# Sheet1_-.net
KiCad netlist of a schematic drawn in Altium Designer
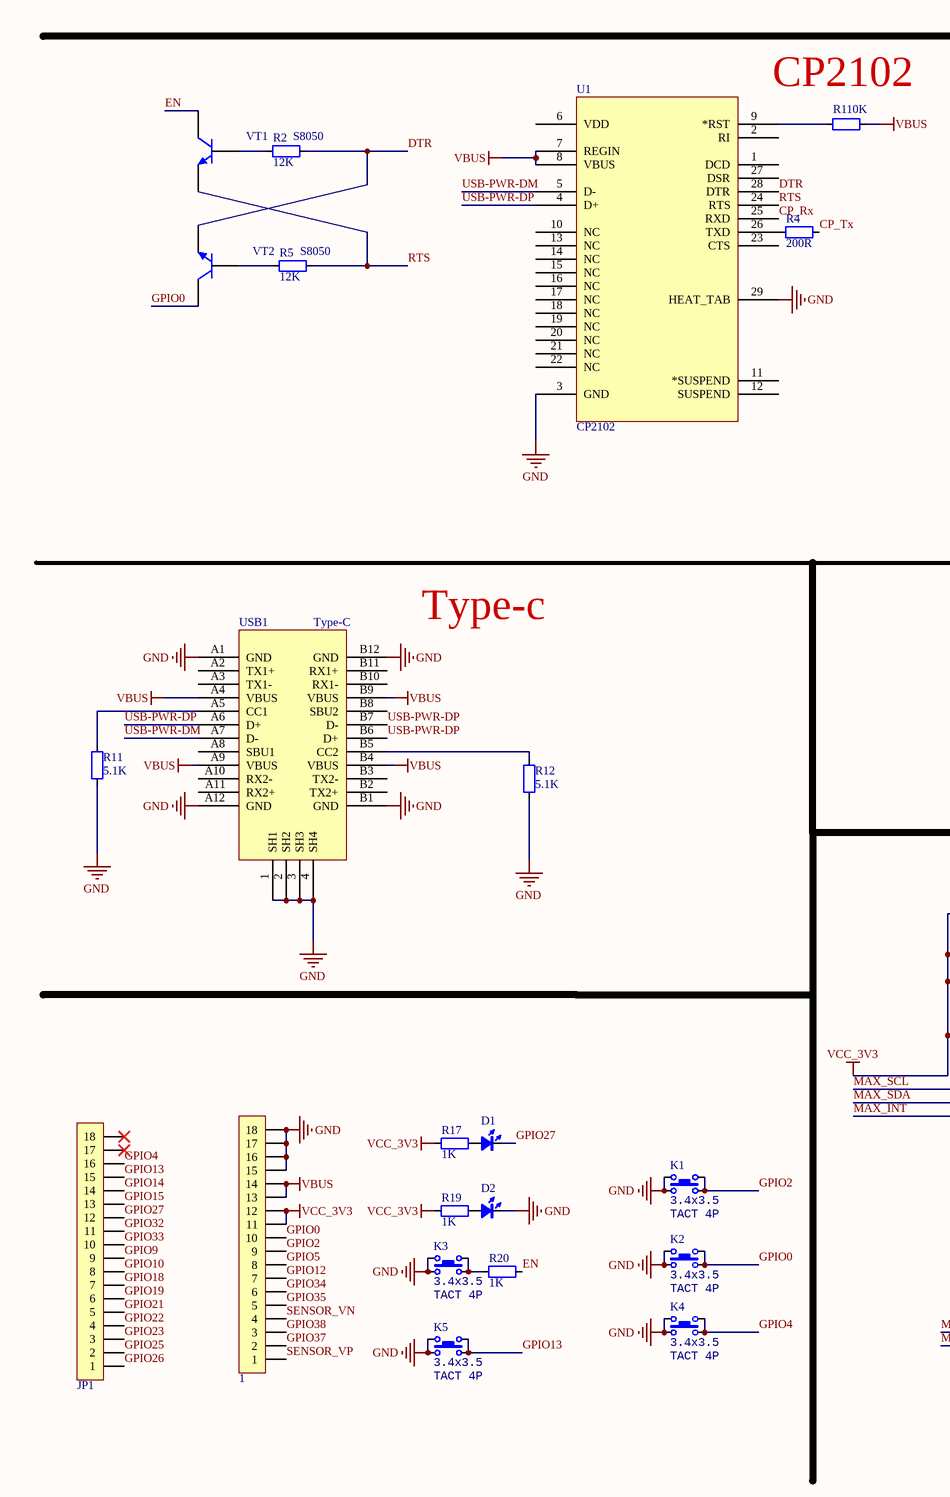
[diagram p0: Sheet1 - 副本.SchDoc, left]
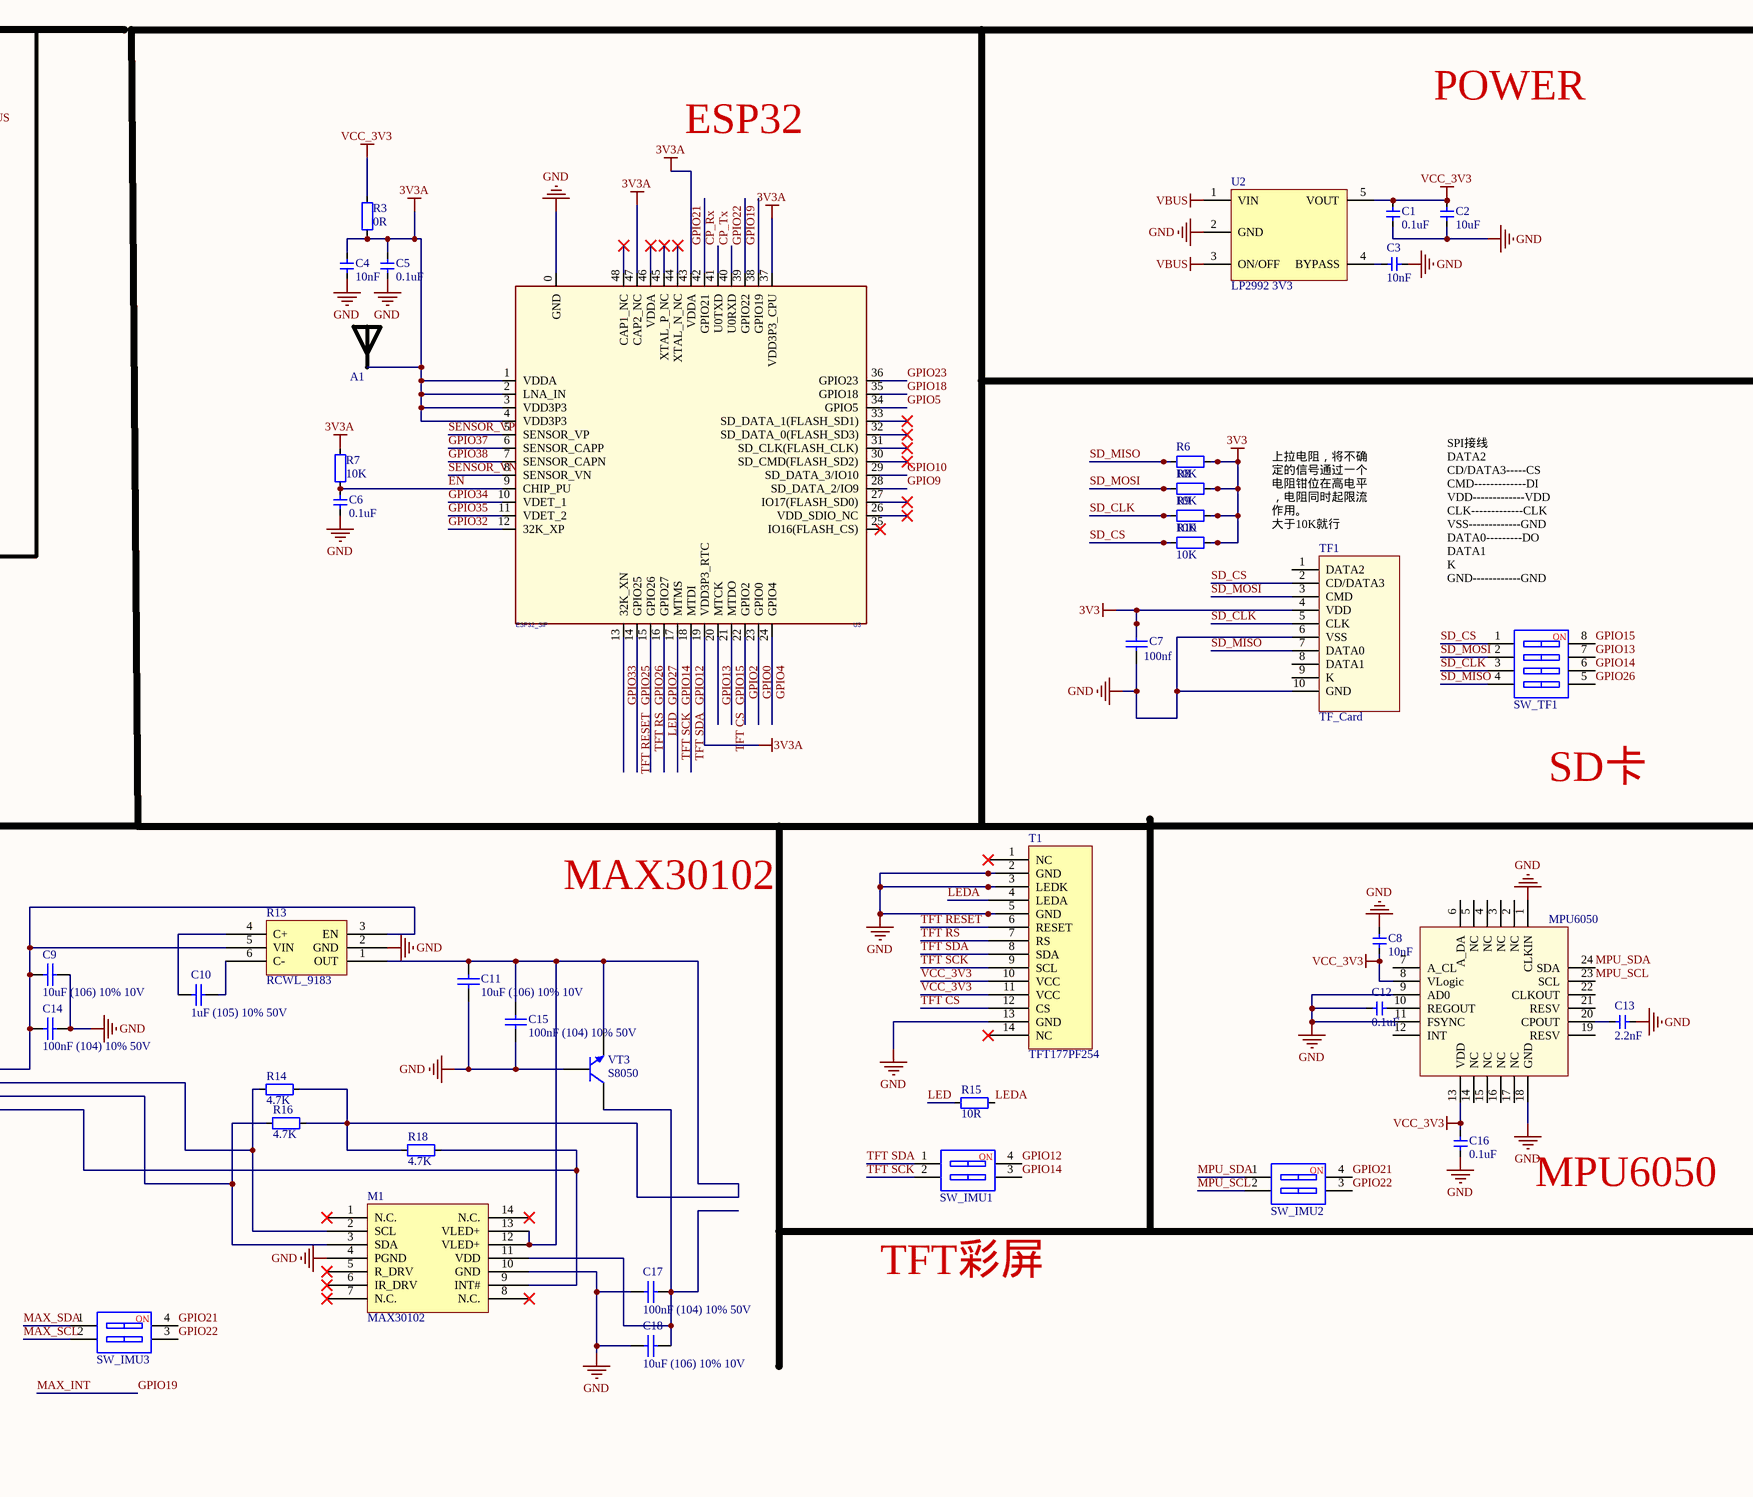
[diagram p1: Sheet1 - 副本.SchDoc, right]

(export (version "E")
  (design (tool "Eeschema 10.0.6"))
  (components
    (comp (ref "1")
      (value "HDR-1X18")
      (footprint "HDR2.54-LI-18P")
      (description "18P接插件")
      (libsource (lib "5.4 - 接插件-脚距2.54 (100mil) ") (part "Header 18"))
    )
    (comp (ref "A1")
      (value "RAINSUN")
      (footprint "ANT-Rainsun-AN5120")
      (libsource (lib "ESP32-PicoDK") (part "ANT-Rainsun-AP5120"))
    )
    (comp (ref "C1")
      (value "0.1uF")
      (footprint "0603_C")
      (description "Capacitor")
      (libsource (lib "MyPcbLib") (part "电容-0402"))
    )
    (comp (ref "C2")
      (value "10uF")
      (footprint "0603_C")
      (description "Capacitor")
      (libsource (lib "MyPcbLib") (part "电容-0402"))
    )
    (comp (ref "C3")
      (value "10nF")
      (footprint "0603_C")
      (description "Capacitor")
      (libsource (lib "MyPcbLib") (part "电容-0402"))
    )
    (comp (ref "C4")
      (value "10nF")
      (footprint "0603_C")
      (description "Capacitor")
      (libsource (lib "ESP32-PicoDK") (part "电容-0402_2"))
    )
    (comp (ref "C5")
      (value "0.1uF")
      (footprint "0603_C")
      (description "Capacitor")
      (libsource (lib "ESP32-PicoDK") (part "电容-0402_1"))
    )
    (comp (ref "C6")
      (value "0.1uF")
      (footprint "0603_C")
      (description "Capacitor")
      (libsource (lib "ESP32-PicoDK") (part "电容-0402_1"))
    )
    (comp (ref "C7")
      (value "100nf")
      (footprint "0603_C")
      (description "Capacitor")
      (libsource (lib "0.1 - 电阻-电容-电感-电位器") (part "C"))
    )
    (comp (ref "C8")
      (value "10nF")
      (footprint "0603_C")
      (description "Capacitor")
      (libsource (lib "MyPcbLib") (part "电容-0402"))
    )
    (comp (ref "C9")
      (value "10uF (106) 10% 10V")
      (footprint "0603_C")
      (description "贴片电容")
      (libsource (lib "Miscellaneous Devices LC") (part "0603 10uF (106) 10% 10V"))
    )
    (comp (ref "C10")
      (value "1uF (105) 10% 50V")
      (footprint "0603_C")
      (description "贴片电容")
      (libsource (lib "Miscellaneous Devices LC") (part "0603 1uF (105) 10% 50V"))
    )
    (comp (ref "C11")
      (value "10uF (106) 10% 10V")
      (footprint "0603_C")
      (description "贴片电容")
      (libsource (lib "Miscellaneous Devices LC") (part "0603 10uF (106) 10% 10V"))
    )
    (comp (ref "C12")
      (value "0.1uF")
      (footprint "0603_C")
      (description "Capacitor")
      (libsource (lib "MyPcbLib") (part "电容-0402"))
    )
    (comp (ref "C13")
      (value "2.2nF")
      (footprint "0603_C")
      (description "Capacitor")
      (libsource (lib "MyPcbLib") (part "电容-0402"))
    )
    (comp (ref "C14")
      (value "100nF (104) 10% 50V")
      (footprint "0603_C")
      (description "贴片电容")
      (libsource (lib "Miscellaneous Devices LC") (part "0603 100nF (104) 10% 50V"))
    )
    (comp (ref "C15")
      (value "100nF (104) 10% 50V")
      (footprint "0603_C")
      (description "贴片电容")
      (libsource (lib "Miscellaneous Devices LC") (part "0603 100nF (104) 10% 50V"))
    )
    (comp (ref "C16")
      (value "0.1uF")
      (footprint "0603_C")
      (description "Capacitor")
      (libsource (lib "MyPcbLib") (part "电容-0402"))
    )
    (comp (ref "C17")
      (value "100nF (104) 10% 50V")
      (footprint "0603_C")
      (description "贴片电容")
      (libsource (lib "Miscellaneous Devices LC") (part "0603 100nF (104) 10% 50V"))
    )
    (comp (ref "C18")
      (value "10uF (106) 10% 10V")
      (footprint "0603_C")
      (description "贴片电容")
      (libsource (lib "Miscellaneous Devices LC") (part "0603 10uF (106) 10% 10V"))
    )
    (comp (ref "D1")
      (value "color?")
      (footprint "LED_0402_RED")
      (description "LED")
      (libsource (lib "KitSprout") (part "LED_0402"))
    )
    (comp (ref "D2")
      (value "color?")
      (footprint "LED_0402_RED")
      (description "LED")
      (libsource (lib "KitSprout") (part "LED_0402"))
    )
    (comp (ref "JP1")
      (value "HDR-1X18")
      (footprint "HDR2.54-LI-18P")
      (description "18P接插件")
      (libsource (lib "5.4 - 接插件-脚距2.54 (100mil) ") (part "Header 18"))
    )
    (comp (ref "K1")
      (value "3.4x3.5")
      (footprint "ButtonTACT_3.5*3.55_90")
      (description "Button")
      (fields (field (name "TYPE") "TACT 4P") (field (name "Comment") "TACT 4P"))
      (libsource (lib "KitSprout") (part "ButtonTACT"))
    )
    (comp (ref "K2")
      (value "3.4x3.5")
      (footprint "ButtonTACT_3.5*3.55_90")
      (description "Button")
      (fields (field (name "TYPE") "TACT 4P") (field (name "Comment") "TACT 4P"))
      (libsource (lib "KitSprout") (part "ButtonTACT"))
    )
    (comp (ref "K3")
      (value "3.4x3.5")
      (footprint "ButtonTACT_3.5*3.55_90")
      (description "Button")
      (fields (field (name "TYPE") "TACT 4P") (field (name "Comment") "TACT 4P"))
      (libsource (lib "KitSprout") (part "ButtonTACT"))
    )
    (comp (ref "K4")
      (value "3.4x3.5")
      (footprint "ButtonTACT_3.5*3.55_90")
      (description "Button")
      (fields (field (name "TYPE") "TACT 4P") (field (name "Comment") "TACT 4P"))
      (libsource (lib "KitSprout") (part "ButtonTACT"))
    )
    (comp (ref "K5")
      (value "3.4x3.5")
      (footprint "ButtonTACT_3.5*3.55_90")
      (description "Button")
      (fields (field (name "TYPE") "TACT 4P") (field (name "Comment") "TACT 4P"))
      (libsource (lib "KitSprout") (part "ButtonTACT"))
    )
    (comp (ref "M1")
      (value "MAX30102")
      (footprint "MAX30102")
      (libsource (lib "ESP32-PicoDK") (part "MAX30102"))
    )
    (comp (ref "R1")
      (value "10K")
      (footprint "0603_R")
      (description "Resistor")
      (libsource (lib "") (part "电阻-0402_1_1"))
    )
    (comp (ref "R2")
      (value "12K")
      (footprint "0603_R")
      (description "Resistor")
      (libsource (lib "ESP32-PicoDK") (part "电阻-0402"))
    )
    (comp (ref "R3")
      (value "0R")
      (footprint "0603_R")
      (description "Resistor")
      (libsource (lib "ESP32-PicoDK") (part "电阻-0402_3"))
    )
    (comp (ref "R4")
      (value "200R")
      (footprint "0603_R")
      (description "Resistor")
      (libsource (lib "ESP32-PicoDK") (part "电阻-0402_2"))
    )
    (comp (ref "R5")
      (value "12K")
      (footprint "0603_R")
      (description "Resistor")
      (libsource (lib "ESP32-PicoDK") (part "电阻-0402"))
    )
    (comp (ref "R6")
      (value "10K")
      (footprint "0603_R")
      (description "贴片电阻")
      (libsource (lib "0.1 - 电阻-电容-电感-电位器") (part "R"))
    )
    (comp (ref "R7")
      (value "10K")
      (footprint "0603_R")
      (description "Resistor")
      (libsource (lib "ESP32-PicoDK") (part "电阻-0402_1"))
    )
    (comp (ref "R8")
      (value "10K")
      (footprint "0603_R")
      (description "贴片电阻")
      (libsource (lib "0.1 - 电阻-电容-电感-电位器") (part "R"))
    )
    (comp (ref "R9")
      (value "10K")
      (footprint "0603_R")
      (description "贴片电阻")
      (libsource (lib "0.1 - 电阻-电容-电感-电位器") (part "R"))
    )
    (comp (ref "R10")
      (value "10K")
      (footprint "0603_R")
      (description "贴片电阻")
      (libsource (lib "0.1 - 电阻-电容-电感-电位器") (part "R"))
    )
    (comp (ref "R11")
      (value "5.1K")
      (footprint "0603_R")
      (description "Resistor")
      (libsource (lib "ESP32-PicoDK") (part "电阻-0402_7"))
    )
    (comp (ref "R12")
      (value "5.1K")
      (footprint "0603_R")
      (description "Resistor")
      (libsource (lib "ESP32-PicoDK") (part "电阻-0402_7"))
    )
    (comp (ref "R13")
      (value "RCWL_9183")
      (footprint "RCWL-9183")
      (libsource (lib "ESP32-PicoDK") (part "RCWL_9183"))
    )
    (comp (ref "R14")
      (value "4.7K")
      (footprint "0603_R")
      (description "Resistor")
      (libsource (lib "ESP32-PicoDK") (part "电阻-0402_6"))
    )
    (comp (ref "R15")
      (value "10R")
      (footprint "0603_R")
      (description "Resistor")
      (libsource (lib "ESP32-PicoDK") (part "电阻-0402_9"))
    )
    (comp (ref "R16")
      (value "4.7K")
      (footprint "0603_R")
      (description "Resistor")
      (libsource (lib "ESP32-PicoDK") (part "电阻-0402_6"))
    )
    (comp (ref "R17")
      (value "1K")
      (footprint "0603_R")
      (description "Resistor")
      (libsource (lib "MyPcbLib") (part "电阻-0402"))
    )
    (comp (ref "R18")
      (value "4.7K")
      (footprint "0603_R")
      (description "Resistor")
      (libsource (lib "ESP32-PicoDK") (part "电阻-0402_6"))
    )
    (comp (ref "R19")
      (value "1K")
      (footprint "0603_R")
      (description "Resistor")
      (libsource (lib "MyPcbLib") (part "电阻-0402"))
    )
    (comp (ref "R20")
      (value "1K")
      (footprint "0603_R")
      (description "Resistor")
      (libsource (lib "MyPcbLib") (part "电阻-0402"))
    )
    (comp (ref "SW_IMU1")
      (value "SW-2P")
      (footprint "SW1.27 SMD-2P")
      (description "2路编码开关")
      (libsource (lib "0.7 - 常用按键-开关-蜂鸣器-电池-测试点") (part "SW-2P"))
    )
    (comp (ref "SW_IMU2")
      (value "SW-2P")
      (footprint "SW1.27 SMD-2P")
      (description "2路编码开关")
      (libsource (lib "0.7 - 常用按键-开关-蜂鸣器-电池-测试点") (part "SW-2P"))
    )
    (comp (ref "SW_IMU3")
      (value "SW-2P")
      (footprint "SW1.27 SMD-2P")
      (description "2路编码开关")
      (libsource (lib "0.7 - 常用按键-开关-蜂鸣器-电池-测试点") (part "SW-2P"))
    )
    (comp (ref "SW_TF1")
      (value "SW-4P")
      (footprint "SW1.27 SMD-4P")
      (description "4路编码开关")
      (libsource (lib "0.7 - 常用按键-开关-蜂鸣器-电池-测试点") (part "SW-4P"))
    )
    (comp (ref "T1")
      (value "TFT177PF254")
      (footprint "TFT144PF254")
      (libsource (lib "ESP32-PicoDK") (part "TFT177PF254"))
    )
    (comp (ref "TF1")
      (value "TF_Card")
      (footprint "Micro SD")
      (description "TF卡座")
      (libsource (lib "0.8 - 以太网-音频-Type-C USB插座") (part "TF_Card"))
    )
    (comp (ref "U1")
      (value "CP2102")
      (footprint "QFN-28")
      (description "USB转TTL")
      (libsource (lib "ESP32-PicoDK") (part "CP2102"))
    )
    (comp (ref "U2")
      (value "LP2992 3V3")
      (footprint "SOT23-5")
      (description "LDO")
      (libsource (lib "MyPcbLib") (part "LP2992"))
    )
    (comp (ref "U3")
      (value "ESP32_SIP")
      (footprint "QFN-48_7X7")
      (libsource (lib "ESP32-PicoDK") (part "ESP32-PICO"))
    )
    (comp (ref "U4")
      (value "MPU6050")
      (footprint "QFN-24")
      (description "六轴传感器")
      (libsource (lib "mLib") (part "MPU6050"))
    )
    (comp (ref "USB1")
      (value "Type-C")
      (footprint "Type-C-TOP")
      (libsource (lib "ESP32-PicoDK") (part "USB-Type-C-TOP"))
    )
    (comp (ref "VT1")
      (value "S8050")
      (footprint "SMT_TRIODE_NPN")
      (description "Surface mount NPN transistor, package SOT-23")
      (libsource (lib "MyPcbLib") (part "SMT_TRIODE_NPN"))
    )
    (comp (ref "VT2")
      (value "S8050")
      (footprint "SMT_TRIODE_NPN")
      (description "Surface mount NPN transistor, package SOT-23")
      (libsource (lib "ESP32-PicoDK") (part "SMT_TRIODE_NPN"))
    )
    (comp (ref "VT3")
      (value "S8050")
      (footprint "SMT_TRIODE_NPN")
      (description "Surface mount NPN transistor, package SOT-23")
      (libsource (lib "ESP32-PicoDK") (part "65k5"))
    )
  )
  (nets
    (net (code "1") (name "/CP_Rx") (class "Default")
      (node (ref "U1") (pin "25") (pinfunction "RXD_25") (pintype "passive"))
      (node (ref "U3") (pin "41") (pinfunction "U0TXD_41") (pintype "power_in"))
    )
    (net (code "2") (name "/CP_Tx") (class "Default")
      (node (ref "R4") (pin "2") (pinfunction "2_2") (pintype "passive"))
      (node (ref "U3") (pin "40") (pinfunction "U0RXD_40") (pintype "power_in"))
    )
    (net (code "3") (name "/DTR") (class "Default")
      (node (ref "R2") (pin "2") (pinfunction "2_2") (pintype "passive"))
      (node (ref "U1") (pin "28") (pinfunction "DTR_28") (pintype "passive"))
      (node (ref "VT2") (pin "2") (pinfunction "E_2") (pintype "passive"))
    )
    (net (code "4") (name "/EN") (class "Default")
      (node (ref "C6") (pin "2") (pinfunction "2_2") (pintype "passive"))
      (node (ref "R20") (pin "2") (pinfunction "2_2") (pintype "passive"))
      (node (ref "R7") (pin "1") (pinfunction "1_1") (pintype "passive"))
      (node (ref "U3") (pin "9") (pinfunction "CHIP_PU_9") (pintype "passive"))
      (node (ref "VT1") (pin "3") (pinfunction "C_3") (pintype "passive"))
    )
    (net (code "5") (name "/GPIO0") (class "Default")
      (node (ref "1") (pin "10") (pinfunction "10_10") (pintype "passive"))
      (node (ref "K2") (pin "2") (pinfunction "2_2") (pintype "passive"))
      (node (ref "K2") (pin "4") (pinfunction "4_4") (pintype "passive"))
      (node (ref "U3") (pin "23") (pinfunction "GPIO0_23") (pintype "passive"))
      (node (ref "VT2") (pin "3") (pinfunction "C_3") (pintype "passive"))
    )
    (net (code "6") (name "/GPIO2") (class "Default")
      (node (ref "1") (pin "9") (pinfunction "9_9") (pintype "passive"))
      (node (ref "K1") (pin "2") (pinfunction "2_2") (pintype "passive"))
      (node (ref "K1") (pin "4") (pinfunction "4_4") (pintype "passive"))
      (node (ref "U3") (pin "22") (pinfunction "GPIO2_22") (pintype "passive"))
    )
    (net (code "7") (name "/GPIO4") (class "Default")
      (node (ref "JP1") (pin "16") (pinfunction "16_16") (pintype "passive"))
      (node (ref "K4") (pin "2") (pinfunction "2_2") (pintype "passive"))
      (node (ref "K4") (pin "4") (pinfunction "4_4") (pintype "passive"))
      (node (ref "U3") (pin "24") (pinfunction "GPIO4_24") (pintype "passive"))
    )
    (net (code "8") (name "/GPIO5") (class "Default")
      (node (ref "1") (pin "8") (pinfunction "8_8") (pintype "passive"))
      (node (ref "U3") (pin "34") (pinfunction "GPIO5_34") (pintype "passive"))
    )
    (net (code "9") (name "/GPIO9") (class "Default")
      (node (ref "JP1") (pin "9") (pinfunction "9_9") (pintype "passive"))
      (node (ref "U3") (pin "28") (pinfunction "SD_DATA_2/IO9_28") (pintype "passive"))
    )
    (net (code "10") (name "/GPIO10") (class "Default")
      (node (ref "JP1") (pin "8") (pinfunction "8_8") (pintype "passive"))
      (node (ref "U3") (pin "29") (pinfunction "SD_DATA_3/IO10_29") (pintype "passive"))
    )
    (net (code "11") (name "/GPIO12") (class "Default")
      (node (ref "1") (pin "7") (pinfunction "7_7") (pintype "passive"))
      (node (ref "SW_IMU1") (pin "1") (pinfunction "1_1") (pintype "passive"))
      (node (ref "SW_IMU1") (pin "4") (pinfunction "4_4") (pintype "passive"))
      (node (ref "T1") (pin "8") (pinfunction "SDA_8") (pintype "open_collector"))
      (node (ref "U3") (pin "18") (pinfunction "MTDI_18") (pintype "passive"))
    )
    (net (code "12") (name "/GPIO13") (class "Default")
      (node (ref "JP1") (pin "15") (pinfunction "15_15") (pintype "passive"))
      (node (ref "K5") (pin "2") (pinfunction "2_2") (pintype "passive"))
      (node (ref "K5") (pin "4") (pinfunction "4_4") (pintype "passive"))
      (node (ref "SW_TF1") (pin "7") (pinfunction "7_7") (pintype "passive"))
      (node (ref "U3") (pin "20") (pinfunction "MTCK_20") (pintype "passive"))
    )
    (net (code "13") (name "/GPIO14") (class "Default")
      (node (ref "JP1") (pin "14") (pinfunction "14_14") (pintype "passive"))
      (node (ref "SW_IMU1") (pin "2") (pinfunction "2_2") (pintype "passive"))
      (node (ref "SW_IMU1") (pin "3") (pinfunction "3_3") (pintype "passive"))
      (node (ref "SW_TF1") (pin "6") (pinfunction "6_6") (pintype "passive"))
      (node (ref "T1") (pin "9") (pinfunction "SCL_9") (pintype "open_collector"))
      (node (ref "U3") (pin "17") (pinfunction "MTMS_17") (pintype "passive"))
    )
    (net (code "14") (name "/GPIO15") (class "Default")
      (node (ref "JP1") (pin "13") (pinfunction "13_13") (pintype "passive"))
      (node (ref "SW_TF1") (pin "8") (pinfunction "8_8") (pintype "passive"))
      (node (ref "T1") (pin "12") (pinfunction "CS_12") (pintype "open_collector"))
      (node (ref "U3") (pin "21") (pinfunction "MTDO_21") (pintype "passive"))
    )
    (net (code "15") (name "/GPIO18") (class "Default")
      (node (ref "JP1") (pin "7") (pinfunction "7_7") (pintype "passive"))
      (node (ref "U3") (pin "35") (pinfunction "GPIO18_35") (pintype "passive"))
    )
    (net (code "16") (name "/GPIO19") (class "Default")
      (node (ref "JP1") (pin "6") (pinfunction "6_6") (pintype "passive"))
      (node (ref "M1") (pin "9") (pinfunction "INT#_9") (pintype "passive"))
      (node (ref "R18") (pin "2") (pinfunction "2_2") (pintype "passive"))
      (node (ref "U3") (pin "38") (pinfunction "GPIO19_38") (pintype "passive"))
    )
    (net (code "17") (name "/GPIO21") (class "Default")
      (node (ref "JP1") (pin "5") (pinfunction "5_5") (pintype "passive"))
      (node (ref "SW_IMU2") (pin "4") (pinfunction "4_4") (pintype "passive"))
      (node (ref "SW_IMU3") (pin "4") (pinfunction "4_4") (pintype "passive"))
      (node (ref "U3") (pin "42") (pinfunction "GPIO21_42") (pintype "passive"))
    )
    (net (code "18") (name "/GPIO22") (class "Default")
      (node (ref "JP1") (pin "4") (pinfunction "4_4") (pintype "passive"))
      (node (ref "SW_IMU2") (pin "3") (pinfunction "3_3") (pintype "passive"))
      (node (ref "SW_IMU3") (pin "3") (pinfunction "3_3") (pintype "passive"))
      (node (ref "U3") (pin "39") (pinfunction "GPIO22_39") (pintype "passive"))
    )
    (net (code "19") (name "/GPIO23") (class "Default")
      (node (ref "JP1") (pin "3") (pinfunction "3_3") (pintype "passive"))
      (node (ref "U3") (pin "36") (pinfunction "GPIO23_36") (pintype "passive"))
    )
    (net (code "20") (name "/GPIO25") (class "Default")
      (node (ref "JP1") (pin "2") (pinfunction "2_2") (pintype "passive"))
      (node (ref "T1") (pin "6") (pinfunction "RESET_6") (pintype "open_collector"))
      (node (ref "U3") (pin "14") (pinfunction "GPIO25_14") (pintype "passive"))
    )
    (net (code "21") (name "/GPIO26") (class "Default")
      (node (ref "JP1") (pin "1") (pinfunction "1_1") (pintype "passive"))
      (node (ref "SW_TF1") (pin "5") (pinfunction "5_5") (pintype "passive"))
      (node (ref "T1") (pin "7") (pinfunction "RS_7") (pintype "open_collector"))
      (node (ref "U3") (pin "15") (pinfunction "GPIO26_15") (pintype "passive"))
    )
    (net (code "22") (name "/GPIO27") (class "Default")
      (node (ref "D1") (pin "2") (pinfunction "K_2") (pintype "passive"))
      (node (ref "JP1") (pin "12") (pinfunction "12_12") (pintype "passive"))
      (node (ref "R15") (pin "1") (pinfunction "1_1") (pintype "passive"))
      (node (ref "U3") (pin "16") (pinfunction "GPIO27_16") (pintype "passive"))
    )
    (net (code "23") (name "/GPIO32") (class "Default")
      (node (ref "JP1") (pin "11") (pinfunction "11_11") (pintype "passive"))
      (node (ref "U3") (pin "12") (pinfunction "32K_XP_12") (pintype "passive"))
    )
    (net (code "24") (name "/GPIO33") (class "Default")
      (node (ref "JP1") (pin "10") (pinfunction "10_10") (pintype "passive"))
      (node (ref "U3") (pin "13") (pinfunction "32K_XN_13") (pintype "passive"))
    )
    (net (code "25") (name "/GPIO34") (class "Default")
      (node (ref "1") (pin "6") (pinfunction "6_6") (pintype "passive"))
      (node (ref "U3") (pin "10") (pinfunction "VDET_1_10") (pintype "passive"))
    )
    (net (code "26") (name "/GPIO35") (class "Default")
      (node (ref "1") (pin "5") (pinfunction "5_5") (pintype "passive"))
      (node (ref "U3") (pin "11") (pinfunction "VDET_2_11") (pintype "passive"))
    )
    (net (code "27") (name "/GPIO37") (class "Default")
      (node (ref "1") (pin "2") (pinfunction "2_2") (pintype "passive"))
      (node (ref "U3") (pin "6") (pinfunction "SENSOR_CAPP_6") (pintype "passive"))
    )
    (net (code "28") (name "/GPIO38") (class "Default")
      (node (ref "1") (pin "3") (pinfunction "3_3") (pintype "passive"))
      (node (ref "U3") (pin "7") (pinfunction "SENSOR_CAPN_7") (pintype "passive"))
    )
    (net (code "29") (name "/LEDA") (class "Default")
      (node (ref "R15") (pin "2") (pinfunction "2_2") (pintype "passive"))
      (node (ref "T1") (pin "4") (pinfunction "LEDA_4") (pintype "open_collector"))
    )
    (net (code "30") (name "/MAX_SCL") (class "Default")
      (node (ref "M1") (pin "2") (pinfunction "SCL_2") (pintype "passive"))
      (node (ref "R14") (pin "1") (pinfunction "1_1") (pintype "passive"))
      (node (ref "SW_IMU3") (pin "2") (pinfunction "2_2") (pintype "passive"))
    )
    (net (code "31") (name "/MAX_SDA") (class "Default")
      (node (ref "M1") (pin "3") (pinfunction "SDA_3") (pintype "passive"))
      (node (ref "R16") (pin "1") (pinfunction "1_1") (pintype "passive"))
      (node (ref "SW_IMU3") (pin "1") (pinfunction "1_1") (pintype "passive"))
    )
    (net (code "32") (name "/MPU_SCL") (class "Default")
      (node (ref "SW_IMU2") (pin "2") (pinfunction "2_2") (pintype "passive"))
      (node (ref "U4") (pin "23") (pinfunction "SCL_23") (pintype "passive"))
    )
    (net (code "33") (name "/MPU_SDA") (class "Default")
      (node (ref "SW_IMU2") (pin "1") (pinfunction "1_1") (pintype "passive"))
      (node (ref "U4") (pin "24") (pinfunction "SDA_24") (pintype "passive"))
    )
    (net (code "34") (name "/RTS") (class "Default")
      (node (ref "R5") (pin "2") (pinfunction "2_2") (pintype "passive"))
      (node (ref "U1") (pin "24") (pinfunction "RTS_24") (pintype "passive"))
      (node (ref "VT1") (pin "2") (pinfunction "E_2") (pintype "passive"))
    )
    (net (code "35") (name "/SD_CLK") (class "Default")
      (node (ref "R9") (pin "1") (pinfunction "1_1") (pintype "passive"))
      (node (ref "SW_TF1") (pin "3") (pinfunction "3_3") (pintype "passive"))
      (node (ref "TF1") (pin "5") (pinfunction "CLK_5") (pintype "passive"))
    )
    (net (code "36") (name "/SD_CS") (class "Default")
      (node (ref "R10") (pin "1") (pinfunction "1_1") (pintype "passive"))
      (node (ref "SW_TF1") (pin "1") (pinfunction "1_1") (pintype "passive"))
      (node (ref "TF1") (pin "2") (pinfunction "CD/DATA3_2") (pintype "passive"))
    )
    (net (code "37") (name "/SD_MISO") (class "Default")
      (node (ref "R6") (pin "1") (pinfunction "1_1") (pintype "passive"))
      (node (ref "SW_TF1") (pin "4") (pinfunction "4_4") (pintype "passive"))
      (node (ref "TF1") (pin "7") (pinfunction "DATA0_7") (pintype "passive"))
    )
    (net (code "38") (name "/SD_MOSI") (class "Default")
      (node (ref "R8") (pin "1") (pinfunction "1_1") (pintype "passive"))
      (node (ref "SW_TF1") (pin "2") (pinfunction "2_2") (pintype "passive"))
      (node (ref "TF1") (pin "3") (pinfunction "CMD_3") (pintype "passive"))
    )
    (net (code "39") (name "/SENSOR_VN") (class "Default")
      (node (ref "1") (pin "4") (pinfunction "4_4") (pintype "passive"))
      (node (ref "U3") (pin "8") (pinfunction "SENSOR_VN_8") (pintype "passive"))
    )
    (net (code "40") (name "/SENSOR_VP") (class "Default")
      (node (ref "1") (pin "1") (pinfunction "1_1") (pintype "passive"))
      (node (ref "U3") (pin "5") (pinfunction "SENSOR_VP_5") (pintype "passive"))
    )
    (net (code "41") (name "/USB-PWR-DM") (class "Default")
      (node (ref "U1") (pin "5") (pinfunction "D-_5") (pintype "passive"))
      (node (ref "USB1") (pin "A7") (pinfunction "D-_A7") (pintype "passive"))
    )
    (net (code "42") (name "/USB-PWR-DP") (class "Default")
      (node (ref "U1") (pin "4") (pinfunction "D+_4") (pintype "passive"))
      (node (ref "USB1") (pin "A6") (pinfunction "D+_A6") (pintype "passive"))
      (node (ref "USB1") (pin "B6") (pinfunction "D+_B6") (pintype "passive"))
      (node (ref "USB1") (pin "B7") (pinfunction "D-_B7") (pintype "passive"))
    )
    (net (code "43") (name "3V3") (class "Default")
      (node (ref "C7") (pin "2") (pinfunction "2_2") (pintype "passive"))
      (node (ref "R10") (pin "2") (pinfunction "2_2") (pintype "passive"))
      (node (ref "R6") (pin "2") (pinfunction "2_2") (pintype "passive"))
      (node (ref "R8") (pin "2") (pinfunction "2_2") (pintype "passive"))
      (node (ref "R9") (pin "2") (pinfunction "2_2") (pintype "passive"))
      (node (ref "TF1") (pin "4") (pinfunction "VDD_4") (pintype "passive"))
    )
    (net (code "44") (name "3V3A") (class "Default")
      (node (ref "A1") (pin "1") (pinfunction "1_1") (pintype "passive"))
      (node (ref "C4") (pin "2") (pinfunction "2_2") (pintype "passive"))
      (node (ref "C5") (pin "2") (pinfunction "2_2") (pintype "passive"))
      (node (ref "R3") (pin "1") (pinfunction "1_1") (pintype "passive"))
      (node (ref "R7") (pin "2") (pinfunction "2_2") (pintype "passive"))
      (node (ref "U3") (pin "1") (pinfunction "VDDA_1") (pintype "power_in"))
      (node (ref "U3") (pin "19") (pinfunction "VDD3P3_RTC_19") (pintype "power_in"))
      (node (ref "U3") (pin "2") (pinfunction "LNA_IN_2") (pintype "passive"))
      (node (ref "U3") (pin "3") (pinfunction "VDD3P3_3") (pintype "power_in"))
      (node (ref "U3") (pin "37") (pinfunction "VDD3P3_CPU_37") (pintype "power_in"))
      (node (ref "U3") (pin "4") (pinfunction "VDD3P3_4") (pintype "power_in"))
      (node (ref "U3") (pin "43") (pinfunction "VDDA_43") (pintype "power_in"))
      (node (ref "U3") (pin "47") (pinfunction "CAP2_NC_47") (pintype "passive"))
    )
    (net (code "45") (name "GND") (class "Default")
      (node (ref "1") (pin "15") (pinfunction "15_15") (pintype "passive"))
      (node (ref "1") (pin "16") (pinfunction "16_16") (pintype "passive"))
      (node (ref "1") (pin "17") (pinfunction "17_17") (pintype "passive"))
      (node (ref "1") (pin "18") (pinfunction "18_18") (pintype "passive"))
      (node (ref "C1") (pin "1") (pinfunction "1_1") (pintype "passive"))
      (node (ref "C11") (pin "1") (pinfunction "1_1") (pintype "passive"))
      (node (ref "C12") (pin "2") (pinfunction "2_2") (pintype "passive"))
      (node (ref "C13") (pin "1") (pinfunction "1_1") (pintype "passive"))
      (node (ref "C14") (pin "2") (pinfunction "2_2") (pintype "passive"))
      (node (ref "C15") (pin "1") (pinfunction "1_1") (pintype "passive"))
      (node (ref "C16") (pin "1") (pinfunction "1_1") (pintype "passive"))
      (node (ref "C17") (pin "2") (pinfunction "2_2") (pintype "passive"))
      (node (ref "C18") (pin "2") (pinfunction "2_2") (pintype "passive"))
      (node (ref "C2") (pin "1") (pinfunction "1_1") (pintype "passive"))
      (node (ref "C3") (pin "1") (pinfunction "1_1") (pintype "passive"))
      (node (ref "C4") (pin "1") (pinfunction "1_1") (pintype "passive"))
      (node (ref "C5") (pin "1") (pinfunction "1_1") (pintype "passive"))
      (node (ref "C6") (pin "1") (pinfunction "1_1") (pintype "passive"))
      (node (ref "C7") (pin "1") (pinfunction "1_1") (pintype "passive"))
      (node (ref "C8") (pin "2") (pinfunction "2_2") (pintype "passive"))
      (node (ref "C9") (pin "2") (pinfunction "2_2") (pintype "passive"))
      (node (ref "D2") (pin "2") (pinfunction "K_2") (pintype "passive"))
      (node (ref "K1") (pin "1") (pinfunction "1_1") (pintype "passive"))
      (node (ref "K1") (pin "3") (pinfunction "3_3") (pintype "passive"))
      (node (ref "K2") (pin "1") (pinfunction "1_1") (pintype "passive"))
      (node (ref "K2") (pin "3") (pinfunction "3_3") (pintype "passive"))
      (node (ref "K3") (pin "1") (pinfunction "1_1") (pintype "passive"))
      (node (ref "K3") (pin "3") (pinfunction "3_3") (pintype "passive"))
      (node (ref "K4") (pin "1") (pinfunction "1_1") (pintype "passive"))
      (node (ref "K4") (pin "3") (pinfunction "3_3") (pintype "passive"))
      (node (ref "K5") (pin "1") (pinfunction "1_1") (pintype "passive"))
      (node (ref "K5") (pin "3") (pinfunction "3_3") (pintype "passive"))
      (node (ref "M1") (pin "10") (pinfunction "GND_10") (pintype "passive"))
      (node (ref "M1") (pin "4") (pinfunction "PGND_4") (pintype "passive"))
      (node (ref "R11") (pin "2") (pinfunction "2_2") (pintype "passive"))
      (node (ref "R12") (pin "2") (pinfunction "2_2") (pintype "passive"))
      (node (ref "R13") (pin "2") (pinfunction "GND_2") (pintype "passive"))
      (node (ref "T1") (pin "13") (pinfunction "GND_13") (pintype "open_collector"))
      (node (ref "T1") (pin "2") (pinfunction "GND_2") (pintype "open_collector"))
      (node (ref "T1") (pin "3") (pinfunction "LEDK_3") (pintype "open_collector"))
      (node (ref "T1") (pin "5") (pinfunction "GND_5") (pintype "open_collector"))
      (node (ref "TF1") (pin "10") (pinfunction "GND_10") (pintype "passive"))
      (node (ref "TF1") (pin "6") (pinfunction "VSS_6") (pintype "passive"))
      (node (ref "U1") (pin "29") (pinfunction "HEAT_TAB_29") (pintype "passive"))
      (node (ref "U1") (pin "3") (pinfunction "GND_3") (pintype "passive"))
      (node (ref "U2") (pin "2") (pinfunction "GND_2") (pintype "passive"))
      (node (ref "U3") (pin "0") (pinfunction "GND_0") (pintype "power_in"))
      (node (ref "U4") (pin "1") (pinfunction "CLKIN_1") (pintype "passive"))
      (node (ref "U4") (pin "11") (pinfunction "FSYNC_11") (pintype "passive"))
      (node (ref "U4") (pin "18") (pinfunction "GND_18") (pintype "passive"))
      (node (ref "U4") (pin "9") (pinfunction "AD0_9") (pintype "passive"))
      (node (ref "USB1") (pin "1") (pinfunction "SH1_1") (pintype "passive"))
      (node (ref "USB1") (pin "2") (pinfunction "SH2_2") (pintype "passive"))
      (node (ref "USB1") (pin "3") (pinfunction "SH3_3") (pintype "passive"))
      (node (ref "USB1") (pin "4") (pinfunction "SH4_4") (pintype "passive"))
      (node (ref "USB1") (pin "A1") (pinfunction "GND_A1") (pintype "passive"))
      (node (ref "USB1") (pin "A12") (pinfunction "GND_A12") (pintype "passive"))
      (node (ref "USB1") (pin "B1") (pinfunction "GND_B1") (pintype "passive"))
      (node (ref "USB1") (pin "B12") (pinfunction "GND_B12") (pintype "passive"))
      (node (ref "VT3") (pin "1") (pinfunction "B_1") (pintype "passive"))
    )
    (net (code "46") (name "Net-(D1-A)") (class "Default")
      (node (ref "D1") (pin "1") (pinfunction "A_1") (pintype "passive"))
      (node (ref "R17") (pin "2") (pinfunction "2_2") (pintype "passive"))
    )
    (net (code "47") (name "Net-(D2-A)") (class "Default")
      (node (ref "D2") (pin "1") (pinfunction "A_1") (pintype "passive"))
      (node (ref "R19") (pin "2") (pinfunction "2_2") (pintype "passive"))
    )
    (net (code "48") (name "Net-(K3-Pad2)") (class "Default")
      (node (ref "K3") (pin "2") (pinfunction "2_2") (pintype "passive"))
      (node (ref "K3") (pin "4") (pinfunction "4_4") (pintype "passive"))
      (node (ref "R20") (pin "1") (pinfunction "1_1") (pintype "passive"))
    )
    (net (code "49") (name "Net-(M1-VDD)") (class "Default")
      (node (ref "C17") (pin "1") (pinfunction "1_1") (pintype "passive"))
      (node (ref "C18") (pin "1") (pinfunction "1_1") (pintype "passive"))
      (node (ref "M1") (pin "11") (pinfunction "VDD_11") (pintype "passive"))
      (node (ref "VT3") (pin "3") (pinfunction "C_3") (pintype "passive"))
    )
    (net (code "50") (name "Net-(R13-C+)") (class "Default")
      (node (ref "C10") (pin "1") (pinfunction "1_1") (pintype "passive"))
      (node (ref "R13") (pin "4") (pinfunction "C+_4") (pintype "passive"))
    )
    (net (code "51") (name "Net-(R13-C-)") (class "Default")
      (node (ref "C10") (pin "2") (pinfunction "2_2") (pintype "passive"))
      (node (ref "R13") (pin "6") (pinfunction "C-_6") (pintype "passive"))
    )
    (net (code "52") (name "Net-(R13-OUT)") (class "Default")
      (node (ref "C11") (pin "2") (pinfunction "2_2") (pintype "passive"))
      (node (ref "C15") (pin "2") (pinfunction "2_2") (pintype "passive"))
      (node (ref "M1") (pin "12") (pinfunction "VLED+_12") (pintype "passive"))
      (node (ref "M1") (pin "13") (pinfunction "VLED+_13") (pintype "passive"))
      (node (ref "R13") (pin "1") (pinfunction "OUT_1") (pintype "passive"))
      (node (ref "R14") (pin "2") (pinfunction "2_2") (pintype "passive"))
      (node (ref "R16") (pin "2") (pinfunction "2_2") (pintype "passive"))
      (node (ref "R18") (pin "1") (pinfunction "1_1") (pintype "passive"))
      (node (ref "VT3") (pin "2") (pinfunction "E_2") (pintype "passive"))
    )
    (net (code "53") (name "Net-(U1-*RST)") (class "Default")
      (node (ref "R1") (pin "1") (pinfunction "1_1") (pintype "passive"))
      (node (ref "U1") (pin "9") (pinfunction "*RST_9") (pintype "passive"))
    )
    (net (code "54") (name "Net-(U1-TXD)") (class "Default")
      (node (ref "R4") (pin "1") (pinfunction "1_1") (pintype "passive"))
      (node (ref "U1") (pin "26") (pinfunction "TXD_26") (pintype "passive"))
    )
    (net (code "55") (name "Net-(U2-BYPASS)") (class "Default")
      (node (ref "C3") (pin "2") (pinfunction "2_2") (pintype "passive"))
      (node (ref "U2") (pin "4") (pinfunction "BYPASS_4") (pintype "passive"))
    )
    (net (code "56") (name "Net-(U4-CPOUT)") (class "Default")
      (node (ref "C13") (pin "2") (pinfunction "2_2") (pintype "passive"))
      (node (ref "U4") (pin "20") (pinfunction "CPOUT_20") (pintype "passive"))
    )
    (net (code "57") (name "Net-(U4-REGOUT)") (class "Default")
      (node (ref "C12") (pin "1") (pinfunction "1_1") (pintype "passive"))
      (node (ref "U4") (pin "10") (pinfunction "REGOUT_10") (pintype "passive"))
    )
    (net (code "58") (name "Net-(USB1-CC1)") (class "Default")
      (node (ref "R11") (pin "1") (pinfunction "1_1") (pintype "passive"))
      (node (ref "USB1") (pin "A5") (pinfunction "CC1_A5") (pintype "passive"))
    )
    (net (code "59") (name "Net-(USB1-CC2)") (class "Default")
      (node (ref "R12") (pin "1") (pinfunction "1_1") (pintype "passive"))
      (node (ref "USB1") (pin "B5") (pinfunction "CC2_B5") (pintype "passive"))
    )
    (net (code "60") (name "Net-(VT1-B)") (class "Default")
      (node (ref "R2") (pin "1") (pinfunction "1_1") (pintype "passive"))
      (node (ref "VT1") (pin "1") (pinfunction "B_1") (pintype "passive"))
    )
    (net (code "61") (name "Net-(VT2-B)") (class "Default")
      (node (ref "R5") (pin "1") (pinfunction "1_1") (pintype "passive"))
      (node (ref "VT2") (pin "1") (pinfunction "B_1") (pintype "passive"))
    )
    (net (code "62") (name "VBUS") (class "Default")
      (node (ref "1") (pin "13") (pinfunction "13_13") (pintype "passive"))
      (node (ref "1") (pin "14") (pinfunction "14_14") (pintype "passive"))
      (node (ref "R1") (pin "2") (pinfunction "2_2") (pintype "passive"))
      (node (ref "U1") (pin "7") (pinfunction "REGIN_7") (pintype "passive"))
      (node (ref "U1") (pin "8") (pinfunction "VBUS_8") (pintype "passive"))
      (node (ref "U2") (pin "1") (pinfunction "VIN_1") (pintype "passive"))
      (node (ref "U2") (pin "3") (pinfunction "ON/OFF_3") (pintype "passive"))
      (node (ref "USB1") (pin "A4") (pinfunction "VBUS_A4") (pintype "passive"))
      (node (ref "USB1") (pin "A9") (pinfunction "VBUS_A9") (pintype "passive"))
      (node (ref "USB1") (pin "B4") (pinfunction "VBUS_B4") (pintype "passive"))
      (node (ref "USB1") (pin "B9") (pinfunction "VBUS_B9") (pintype "passive"))
    )
    (net (code "63") (name "VCC_3V3") (class "Default")
      (node (ref "1") (pin "11") (pinfunction "11_11") (pintype "passive"))
      (node (ref "1") (pin "12") (pinfunction "12_12") (pintype "passive"))
      (node (ref "C1") (pin "2") (pinfunction "2_2") (pintype "passive"))
      (node (ref "C14") (pin "1") (pinfunction "1_1") (pintype "passive"))
      (node (ref "C16") (pin "2") (pinfunction "2_2") (pintype "passive"))
      (node (ref "C2") (pin "2") (pinfunction "2_2") (pintype "passive"))
      (node (ref "C8") (pin "1") (pinfunction "1_1") (pintype "passive"))
      (node (ref "C9") (pin "1") (pinfunction "1_1") (pintype "passive"))
      (node (ref "R13") (pin "3") (pinfunction "EN_3") (pintype "passive"))
      (node (ref "R13") (pin "5") (pinfunction "VIN_5") (pintype "passive"))
      (node (ref "R17") (pin "1") (pinfunction "1_1") (pintype "passive"))
      (node (ref "R19") (pin "1") (pinfunction "1_1") (pintype "passive"))
      (node (ref "R3") (pin "2") (pinfunction "2_2") (pintype "passive"))
      (node (ref "T1") (pin "10") (pinfunction "VCC_10") (pintype "open_collector"))
      (node (ref "T1") (pin "11") (pinfunction "VCC_11") (pintype "open_collector"))
      (node (ref "U2") (pin "5") (pinfunction "VOUT_5") (pintype "passive"))
      (node (ref "U4") (pin "13") (pinfunction "VDD_13") (pintype "passive"))
      (node (ref "U4") (pin "8") (pinfunction "VLogic_8") (pintype "passive"))
    )
    (net (code "64") (name "unconnected-(JP1-Pad17)") (class "Default")
      (node (ref "JP1") (pin "17") (pinfunction "17_17") (pintype "passive+no_connect"))
    )
    (net (code "65") (name "unconnected-(JP1-Pad18)") (class "Default")
      (node (ref "JP1") (pin "18") (pinfunction "18_18") (pintype "passive+no_connect"))
    )
    (net (code "66") (name "unconnected-(M1-IR_DRV-Pad6)") (class "Default")
      (node (ref "M1") (pin "6") (pinfunction "IR_DRV_6") (pintype "passive+no_connect"))
    )
    (net (code "67") (name "unconnected-(M1-N.C.-Pad1)") (class "Default")
      (node (ref "M1") (pin "1") (pinfunction "N.C._1") (pintype "passive+no_connect"))
    )
    (net (code "68") (name "unconnected-(M1-N.C.-Pad7)") (class "Default")
      (node (ref "M1") (pin "7") (pinfunction "N.C._7") (pintype "passive+no_connect"))
    )
    (net (code "69") (name "unconnected-(M1-N.C.-Pad8)") (class "Default")
      (node (ref "M1") (pin "8") (pinfunction "N.C._8") (pintype "passive+no_connect"))
    )
    (net (code "70") (name "unconnected-(M1-N.C.-Pad14)") (class "Default")
      (node (ref "M1") (pin "14") (pinfunction "N.C._14") (pintype "passive+no_connect"))
    )
    (net (code "71") (name "unconnected-(M1-R_DRV-Pad5)") (class "Default")
      (node (ref "M1") (pin "5") (pinfunction "R_DRV_5") (pintype "passive+no_connect"))
    )
    (net (code "72") (name "unconnected-(T1-NC-Pad1)") (class "Default")
      (node (ref "T1") (pin "1") (pinfunction "NC_1") (pintype "open_collector+no_connect"))
    )
    (net (code "73") (name "unconnected-(T1-NC-Pad14)") (class "Default")
      (node (ref "T1") (pin "14") (pinfunction "NC_14") (pintype "open_collector+no_connect"))
    )
    (net (code "74") (name "unconnected-(TF1-DATA1-Pad8)") (class "Default")
      (node (ref "TF1") (pin "8") (pinfunction "DATA1_8") (pintype "passive"))
    )
    (net (code "75") (name "unconnected-(TF1-DATA2-Pad1)") (class "Default")
      (node (ref "TF1") (pin "1") (pinfunction "DATA2_1") (pintype "passive"))
    )
    (net (code "76") (name "unconnected-(TF1-K-Pad9)") (class "Default")
      (node (ref "TF1") (pin "9") (pinfunction "K_9") (pintype "passive"))
    )
    (net (code "77") (name "unconnected-(U1-*SUSPEND-Pad11)") (class "Default")
      (node (ref "U1") (pin "11") (pinfunction "*SUSPEND_11") (pintype "passive"))
    )
    (net (code "78") (name "unconnected-(U1-CTS-Pad23)") (class "Default")
      (node (ref "U1") (pin "23") (pinfunction "CTS_23") (pintype "passive"))
    )
    (net (code "79") (name "unconnected-(U1-DCD-Pad1)") (class "Default")
      (node (ref "U1") (pin "1") (pinfunction "DCD_1") (pintype "passive"))
    )
    (net (code "80") (name "unconnected-(U1-DSR-Pad27)") (class "Default")
      (node (ref "U1") (pin "27") (pinfunction "DSR_27") (pintype "passive"))
    )
    (net (code "81") (name "unconnected-(U1-NC-Pad10)") (class "Default")
      (node (ref "U1") (pin "10") (pinfunction "NC_10") (pintype "passive"))
    )
    (net (code "82") (name "unconnected-(U1-NC-Pad13)") (class "Default")
      (node (ref "U1") (pin "13") (pinfunction "NC_13") (pintype "passive"))
    )
    (net (code "83") (name "unconnected-(U1-NC-Pad14)") (class "Default")
      (node (ref "U1") (pin "14") (pinfunction "NC_14") (pintype "passive"))
    )
    (net (code "84") (name "unconnected-(U1-NC-Pad15)") (class "Default")
      (node (ref "U1") (pin "15") (pinfunction "NC_15") (pintype "passive"))
    )
    (net (code "85") (name "unconnected-(U1-NC-Pad16)") (class "Default")
      (node (ref "U1") (pin "16") (pinfunction "NC_16") (pintype "passive"))
    )
    (net (code "86") (name "unconnected-(U1-NC-Pad17)") (class "Default")
      (node (ref "U1") (pin "17") (pinfunction "NC_17") (pintype "passive"))
    )
    (net (code "87") (name "unconnected-(U1-NC-Pad18)") (class "Default")
      (node (ref "U1") (pin "18") (pinfunction "NC_18") (pintype "passive"))
    )
    (net (code "88") (name "unconnected-(U1-NC-Pad19)") (class "Default")
      (node (ref "U1") (pin "19") (pinfunction "NC_19") (pintype "passive"))
    )
    (net (code "89") (name "unconnected-(U1-NC-Pad20)") (class "Default")
      (node (ref "U1") (pin "20") (pinfunction "NC_20") (pintype "passive"))
    )
    (net (code "90") (name "unconnected-(U1-NC-Pad21)") (class "Default")
      (node (ref "U1") (pin "21") (pinfunction "NC_21") (pintype "passive"))
    )
    (net (code "91") (name "unconnected-(U1-NC-Pad22)") (class "Default")
      (node (ref "U1") (pin "22") (pinfunction "NC_22") (pintype "passive"))
    )
    (net (code "92") (name "unconnected-(U1-RI-Pad2)") (class "Default")
      (node (ref "U1") (pin "2") (pinfunction "RI_2") (pintype "passive"))
    )
    (net (code "93") (name "unconnected-(U1-SUSPEND-Pad12)") (class "Default")
      (node (ref "U1") (pin "12") (pinfunction "SUSPEND_12") (pintype "passive"))
    )
    (net (code "94") (name "unconnected-(U1-VDD-Pad6)") (class "Default")
      (node (ref "U1") (pin "6") (pinfunction "VDD_6") (pintype "passive"))
    )
    (net (code "95") (name "unconnected-(U3-CAP1_NC-Pad48)") (class "Default")
      (node (ref "U3") (pin "48") (pinfunction "CAP1_NC_48") (pintype "passive+no_connect"))
    )
    (net (code "96") (name "unconnected-(U3-IO16(FLASH_CS)-Pad25)") (class "Default")
      (node (ref "U3") (pin "25") (pinfunction "IO16(FLASH_CS)_25") (pintype "passive+no_connect"))
    )
    (net (code "97") (name "unconnected-(U3-IO17(FLASH_SD0)-Pad27)") (class "Default")
      (node (ref "U3") (pin "27") (pinfunction "IO17(FLASH_SD0)_27") (pintype "passive+no_connect"))
    )
    (net (code "98") (name "unconnected-(U3-SD_CLK(FLASH_CLK)-Pad31)") (class "Default")
      (node (ref "U3") (pin "31") (pinfunction "SD_CLK(FLASH_CLK)_31") (pintype "passive+no_connect"))
    )
    (net (code "99") (name "unconnected-(U3-SD_CMD(FLASH_SD2)-Pad30)") (class "Default")
      (node (ref "U3") (pin "30") (pinfunction "SD_CMD(FLASH_SD2)_30") (pintype "passive+no_connect"))
    )
    (net (code "100") (name "unconnected-(U3-SD_DATA_0(FLASH_SD3)-Pad32)") (class "Default")
      (node (ref "U3") (pin "32") (pinfunction "SD_DATA_0(FLASH_SD3)_32") (pintype "passive+no_connect"))
    )
    (net (code "101") (name "unconnected-(U3-SD_DATA_1(FLASH_SD1)-Pad33)") (class "Default")
      (node (ref "U3") (pin "33") (pinfunction "SD_DATA_1(FLASH_SD1)_33") (pintype "passive+no_connect"))
    )
    (net (code "102") (name "unconnected-(U3-VDDA-Pad46)") (class "Default")
      (node (ref "U3") (pin "46") (pinfunction "VDDA_46") (pintype "power_in+no_connect"))
    )
    (net (code "103") (name "unconnected-(U3-VDD_SDIO_NC-Pad26)") (class "Default")
      (node (ref "U3") (pin "26") (pinfunction "VDD_SDIO_NC_26") (pintype "passive+no_connect"))
    )
    (net (code "104") (name "unconnected-(U3-XTAL_N_NC-Pad44)") (class "Default")
      (node (ref "U3") (pin "44") (pinfunction "XTAL_N_NC_44") (pintype "passive+no_connect"))
    )
    (net (code "105") (name "unconnected-(U3-XTAL_P_NC-Pad45)") (class "Default")
      (node (ref "U3") (pin "45") (pinfunction "XTAL_P_NC_45") (pintype "passive+no_connect"))
    )
    (net (code "106") (name "unconnected-(U4-A_CL-Pad7)") (class "Default")
      (node (ref "U4") (pin "7") (pinfunction "A_CL_7") (pintype "passive"))
    )
    (net (code "107") (name "unconnected-(U4-A_DA-Pad6)") (class "Default")
      (node (ref "U4") (pin "6") (pinfunction "A_DA_6") (pintype "passive"))
    )
    (net (code "108") (name "unconnected-(U4-CLKOUT-Pad22)") (class "Default")
      (node (ref "U4") (pin "22") (pinfunction "CLKOUT_22") (pintype "passive"))
    )
    (net (code "109") (name "unconnected-(U4-INT-Pad12)") (class "Default")
      (node (ref "U4") (pin "12") (pinfunction "INT_12") (pintype "passive"))
    )
    (net (code "110") (name "unconnected-(U4-NC-Pad2)") (class "Default")
      (node (ref "U4") (pin "2") (pinfunction "NC_2") (pintype "passive"))
    )
    (net (code "111") (name "unconnected-(U4-NC-Pad3)") (class "Default")
      (node (ref "U4") (pin "3") (pinfunction "NC_3") (pintype "passive"))
    )
    (net (code "112") (name "unconnected-(U4-NC-Pad4)") (class "Default")
      (node (ref "U4") (pin "4") (pinfunction "NC_4") (pintype "passive"))
    )
    (net (code "113") (name "unconnected-(U4-NC-Pad5)") (class "Default")
      (node (ref "U4") (pin "5") (pinfunction "NC_5") (pintype "passive"))
    )
    (net (code "114") (name "unconnected-(U4-NC-Pad14)") (class "Default")
      (node (ref "U4") (pin "14") (pinfunction "NC_14") (pintype "passive"))
    )
    (net (code "115") (name "unconnected-(U4-NC-Pad15)") (class "Default")
      (node (ref "U4") (pin "15") (pinfunction "NC_15") (pintype "passive"))
    )
    (net (code "116") (name "unconnected-(U4-NC-Pad16)") (class "Default")
      (node (ref "U4") (pin "16") (pinfunction "NC_16") (pintype "passive"))
    )
    (net (code "117") (name "unconnected-(U4-NC-Pad17)") (class "Default")
      (node (ref "U4") (pin "17") (pinfunction "NC_17") (pintype "passive"))
    )
    (net (code "118") (name "unconnected-(U4-RESV-Pad19)") (class "Default")
      (node (ref "U4") (pin "19") (pinfunction "RESV_19") (pintype "passive"))
    )
    (net (code "119") (name "unconnected-(U4-RESV-Pad21)") (class "Default")
      (node (ref "U4") (pin "21") (pinfunction "RESV_21") (pintype "passive"))
    )
    (net (code "120") (name "unconnected-(USB1-RX1+-PadB11)") (class "Default")
      (node (ref "USB1") (pin "B11") (pinfunction "RX1+_B11") (pintype "passive"))
    )
    (net (code "121") (name "unconnected-(USB1-RX1--PadB10)") (class "Default")
      (node (ref "USB1") (pin "B10") (pinfunction "RX1-_B10") (pintype "passive"))
    )
    (net (code "122") (name "unconnected-(USB1-RX2+-PadA11)") (class "Default")
      (node (ref "USB1") (pin "A11") (pinfunction "RX2+_A11") (pintype "passive"))
    )
    (net (code "123") (name "unconnected-(USB1-RX2--PadA10)") (class "Default")
      (node (ref "USB1") (pin "A10") (pinfunction "RX2-_A10") (pintype "passive"))
    )
    (net (code "124") (name "unconnected-(USB1-SBU1-PadA8)") (class "Default")
      (node (ref "USB1") (pin "A8") (pinfunction "SBU1_A8") (pintype "passive"))
    )
    (net (code "125") (name "unconnected-(USB1-SBU2-PadB8)") (class "Default")
      (node (ref "USB1") (pin "B8") (pinfunction "SBU2_B8") (pintype "passive"))
    )
    (net (code "126") (name "unconnected-(USB1-TX1+-PadA2)") (class "Default")
      (node (ref "USB1") (pin "A2") (pinfunction "TX1+_A2") (pintype "passive"))
    )
    (net (code "127") (name "unconnected-(USB1-TX1--PadA3)") (class "Default")
      (node (ref "USB1") (pin "A3") (pinfunction "TX1-_A3") (pintype "passive"))
    )
    (net (code "128") (name "unconnected-(USB1-TX2+-PadB2)") (class "Default")
      (node (ref "USB1") (pin "B2") (pinfunction "TX2+_B2") (pintype "passive"))
    )
    (net (code "129") (name "unconnected-(USB1-TX2--PadB3)") (class "Default")
      (node (ref "USB1") (pin "B3") (pinfunction "TX2-_B3") (pintype "passive"))
    )
  )
)
